# wiring.net
KiCad netlist of a schematic drawn in EAGLE
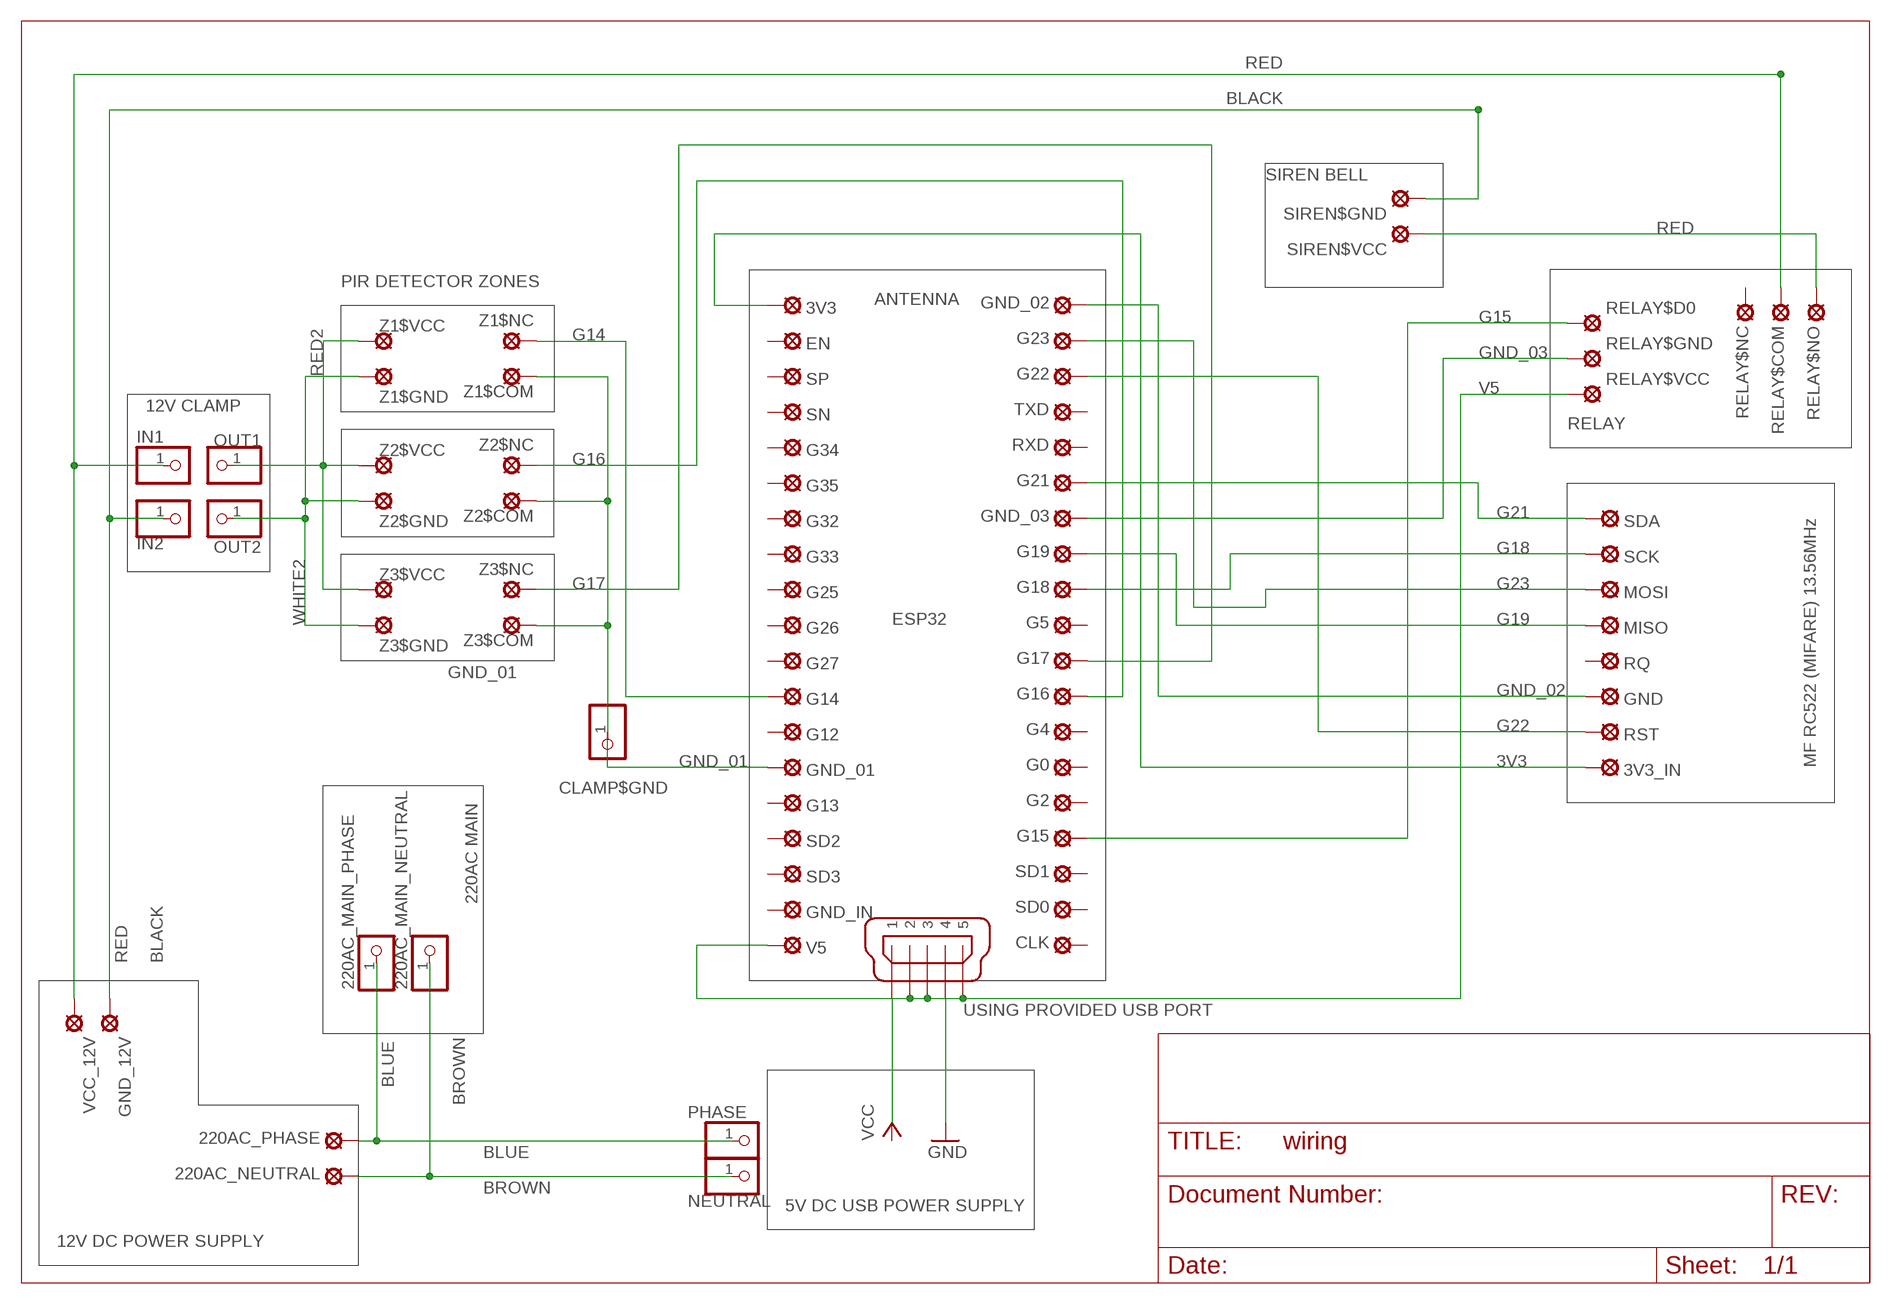
[diagram p0: schematic, sheet 1]

(export (version "E")
  (design (tool "Eeschema 10.0.6"))
  (components
    (comp (ref "3V3")
      (value "MCS08")
      (footprint "eagle-import:MCS08")
      (libsource (lib "eagle-import") (part "MCS08"))
    )
    (comp (ref "3V3_IN")
      (value "MCS08")
      (footprint "eagle-import:MCS08")
      (libsource (lib "eagle-import") (part "MCS08"))
    )
    (comp (ref "220AC_MAIN_NEUTRAL")
      (value "PINHD-1X1")
      (footprint "eagle-import:1X01")
      (libsource (lib "eagle-import") (part "PINHD-1X1"))
    )
    (comp (ref "220AC_MAIN_PHASE")
      (value "PINHD-1X1")
      (footprint "eagle-import:1X01")
      (libsource (lib "eagle-import") (part "PINHD-1X1"))
    )
    (comp (ref "220AC_NEUTRAL")
      (value "MCS08")
      (footprint "eagle-import:MCS08")
      (libsource (lib "eagle-import") (part "MCS08"))
    )
    (comp (ref "220AC_PHASE")
      (value "MCS08")
      (footprint "eagle-import:MCS08")
      (libsource (lib "eagle-import") (part "MCS08"))
    )
    (comp (ref "CLAMP$GND")
      (value "PINHD-1X1")
      (footprint "eagle-import:1X01")
      (libsource (lib "eagle-import") (part "PINHD-1X1"))
    )
    (comp (ref "CLK")
      (value "MCS08")
      (footprint "eagle-import:MCS08")
      (libsource (lib "eagle-import") (part "MCS08"))
    )
    (comp (ref "EN")
      (value "MCS08")
      (footprint "eagle-import:MCS08")
      (libsource (lib "eagle-import") (part "MCS08"))
    )
    (comp (ref "G0")
      (value "MCS08")
      (footprint "eagle-import:MCS08")
      (libsource (lib "eagle-import") (part "MCS08"))
    )
    (comp (ref "G2")
      (value "MCS08")
      (footprint "eagle-import:MCS08")
      (libsource (lib "eagle-import") (part "MCS08"))
    )
    (comp (ref "G4")
      (value "MCS08")
      (footprint "eagle-import:MCS08")
      (libsource (lib "eagle-import") (part "MCS08"))
    )
    (comp (ref "G5")
      (value "MCS08")
      (footprint "eagle-import:MCS08")
      (libsource (lib "eagle-import") (part "MCS08"))
    )
    (comp (ref "G12")
      (value "MCS08")
      (footprint "eagle-import:MCS08")
      (libsource (lib "eagle-import") (part "MCS08"))
    )
    (comp (ref "G13")
      (value "MCS08")
      (footprint "eagle-import:MCS08")
      (libsource (lib "eagle-import") (part "MCS08"))
    )
    (comp (ref "G14")
      (value "MCS08")
      (footprint "eagle-import:MCS08")
      (libsource (lib "eagle-import") (part "MCS08"))
    )
    (comp (ref "G15")
      (value "MCS08")
      (footprint "eagle-import:MCS08")
      (libsource (lib "eagle-import") (part "MCS08"))
    )
    (comp (ref "G16")
      (value "MCS08")
      (footprint "eagle-import:MCS08")
      (libsource (lib "eagle-import") (part "MCS08"))
    )
    (comp (ref "G17")
      (value "MCS08")
      (footprint "eagle-import:MCS08")
      (libsource (lib "eagle-import") (part "MCS08"))
    )
    (comp (ref "G18")
      (value "MCS08")
      (footprint "eagle-import:MCS08")
      (libsource (lib "eagle-import") (part "MCS08"))
    )
    (comp (ref "G19")
      (value "MCS08")
      (footprint "eagle-import:MCS08")
      (libsource (lib "eagle-import") (part "MCS08"))
    )
    (comp (ref "G21")
      (value "MCS08")
      (footprint "eagle-import:MCS08")
      (libsource (lib "eagle-import") (part "MCS08"))
    )
    (comp (ref "G22")
      (value "MCS08")
      (footprint "eagle-import:MCS08")
      (libsource (lib "eagle-import") (part "MCS08"))
    )
    (comp (ref "G23")
      (value "MCS08")
      (footprint "eagle-import:MCS08")
      (libsource (lib "eagle-import") (part "MCS08"))
    )
    (comp (ref "G25")
      (value "MCS08")
      (footprint "eagle-import:MCS08")
      (libsource (lib "eagle-import") (part "MCS08"))
    )
    (comp (ref "G26")
      (value "MCS08")
      (footprint "eagle-import:MCS08")
      (libsource (lib "eagle-import") (part "MCS08"))
    )
    (comp (ref "G27")
      (value "MCS08")
      (footprint "eagle-import:MCS08")
      (libsource (lib "eagle-import") (part "MCS08"))
    )
    (comp (ref "G32")
      (value "MCS08")
      (footprint "eagle-import:MCS08")
      (libsource (lib "eagle-import") (part "MCS08"))
    )
    (comp (ref "G33")
      (value "MCS08")
      (footprint "eagle-import:MCS08")
      (libsource (lib "eagle-import") (part "MCS08"))
    )
    (comp (ref "G34")
      (value "MCS08")
      (footprint "eagle-import:MCS08")
      (libsource (lib "eagle-import") (part "MCS08"))
    )
    (comp (ref "G35")
      (value "MCS08")
      (footprint "eagle-import:MCS08")
      (libsource (lib "eagle-import") (part "MCS08"))
    )
    (comp (ref "GND")
      (value "MCS08")
      (footprint "eagle-import:MCS08")
      (libsource (lib "eagle-import") (part "MCS08"))
    )
    (comp (ref "GND_01")
      (value "MCS08")
      (footprint "eagle-import:MCS08")
      (libsource (lib "eagle-import") (part "MCS08"))
    )
    (comp (ref "GND_02")
      (value "MCS08")
      (footprint "eagle-import:MCS08")
      (libsource (lib "eagle-import") (part "MCS08"))
    )
    (comp (ref "GND_03")
      (value "MCS08")
      (footprint "eagle-import:MCS08")
      (libsource (lib "eagle-import") (part "MCS08"))
    )
    (comp (ref "GND_12V")
      (value "MCS08")
      (footprint "eagle-import:MCS08")
      (libsource (lib "eagle-import") (part "MCS08"))
    )
    (comp (ref "GND_IN")
      (value "MCS08")
      (footprint "eagle-import:MCS08")
      (libsource (lib "eagle-import") (part "MCS08"))
    )
    (comp (ref "IN1")
      (value "PINHD-1X1")
      (footprint "eagle-import:1X01")
      (libsource (lib "eagle-import") (part "PINHD-1X1"))
    )
    (comp (ref "IN2")
      (value "PINHD-1X1")
      (footprint "eagle-import:1X01")
      (libsource (lib "eagle-import") (part "PINHD-1X1"))
    )
    (comp (ref "MISO")
      (value "MCS08")
      (footprint "eagle-import:MCS08")
      (libsource (lib "eagle-import") (part "MCS08"))
    )
    (comp (ref "MOSI")
      (value "MCS08")
      (footprint "eagle-import:MCS08")
      (libsource (lib "eagle-import") (part "MCS08"))
    )
    (comp (ref "NEUTRAL")
      (value "PINHD-1X1")
      (footprint "eagle-import:1X01")
      (libsource (lib "eagle-import") (part "PINHD-1X1"))
    )
    (comp (ref "OUT1")
      (value "PINHD-1X1")
      (footprint "eagle-import:1X01")
      (libsource (lib "eagle-import") (part "PINHD-1X1"))
    )
    (comp (ref "OUT2")
      (value "PINHD-1X1")
      (footprint "eagle-import:1X01")
      (libsource (lib "eagle-import") (part "PINHD-1X1"))
    )
    (comp (ref "PHASE")
      (value "PINHD-1X1")
      (footprint "eagle-import:1X01")
      (libsource (lib "eagle-import") (part "PINHD-1X1"))
    )
    (comp (ref "RELAY$COM")
      (value "MCS08")
      (footprint "eagle-import:MCS08")
      (libsource (lib "eagle-import") (part "MCS08"))
    )
    (comp (ref "RELAY$D0")
      (value "MCS08")
      (footprint "eagle-import:MCS08")
      (libsource (lib "eagle-import") (part "MCS08"))
    )
    (comp (ref "RELAY$GND")
      (value "MCS08")
      (footprint "eagle-import:MCS08")
      (libsource (lib "eagle-import") (part "MCS08"))
    )
    (comp (ref "RELAY$NC")
      (value "MCS08")
      (footprint "eagle-import:MCS08")
      (libsource (lib "eagle-import") (part "MCS08"))
    )
    (comp (ref "RELAY$NO")
      (value "MCS08")
      (footprint "eagle-import:MCS08")
      (libsource (lib "eagle-import") (part "MCS08"))
    )
    (comp (ref "RELAY$VCC")
      (value "MCS08")
      (footprint "eagle-import:MCS08")
      (libsource (lib "eagle-import") (part "MCS08"))
    )
    (comp (ref "RQ")
      (value "MCS08")
      (footprint "eagle-import:MCS08")
      (libsource (lib "eagle-import") (part "MCS08"))
    )
    (comp (ref "RST")
      (value "MCS08")
      (footprint "eagle-import:MCS08")
      (libsource (lib "eagle-import") (part "MCS08"))
    )
    (comp (ref "RXD")
      (value "MCS08")
      (footprint "eagle-import:MCS08")
      (libsource (lib "eagle-import") (part "MCS08"))
    )
    (comp (ref "SCK")
      (value "MCS08")
      (footprint "eagle-import:MCS08")
      (libsource (lib "eagle-import") (part "MCS08"))
    )
    (comp (ref "SD0")
      (value "MCS08")
      (footprint "eagle-import:MCS08")
      (libsource (lib "eagle-import") (part "MCS08"))
    )
    (comp (ref "SD1")
      (value "MCS08")
      (footprint "eagle-import:MCS08")
      (libsource (lib "eagle-import") (part "MCS08"))
    )
    (comp (ref "SD2")
      (value "MCS08")
      (footprint "eagle-import:MCS08")
      (libsource (lib "eagle-import") (part "MCS08"))
    )
    (comp (ref "SD3")
      (value "MCS08")
      (footprint "eagle-import:MCS08")
      (libsource (lib "eagle-import") (part "MCS08"))
    )
    (comp (ref "SDA")
      (value "MCS08")
      (footprint "eagle-import:MCS08")
      (libsource (lib "eagle-import") (part "MCS08"))
    )
    (comp (ref "SIREN$GND")
      (value "MCS08")
      (footprint "eagle-import:MCS08")
      (libsource (lib "eagle-import") (part "MCS08"))
    )
    (comp (ref "SIREN$VCC")
      (value "MCS08")
      (footprint "eagle-import:MCS08")
      (libsource (lib "eagle-import") (part "MCS08"))
    )
    (comp (ref "SN")
      (value "MCS08")
      (footprint "eagle-import:MCS08")
      (libsource (lib "eagle-import") (part "MCS08"))
    )
    (comp (ref "SP")
      (value "MCS08")
      (footprint "eagle-import:MCS08")
      (libsource (lib "eagle-import") (part "MCS08"))
    )
    (comp (ref "TXD")
      (value "MCS08")
      (footprint "eagle-import:MCS08")
      (libsource (lib "eagle-import") (part "MCS08"))
    )
    (comp (ref "V5")
      (value "MCS08")
      (footprint "eagle-import:MCS08")
      (libsource (lib "eagle-import") (part "MCS08"))
    )
    (comp (ref "VCC_12V")
      (value "MCS08")
      (footprint "eagle-import:MCS08")
      (libsource (lib "eagle-import") (part "MCS08"))
    )
    (comp (ref "X1")
      (value "MINI-USB_SHIELD5P2-32005-601")
      (footprint "eagle-import:32005-601")
      (libsource (lib "eagle-import") (part "MINI-USB_SHIELD5P2-32005-601"))
    )
    (comp (ref "Z1$COM")
      (value "MCS08")
      (footprint "eagle-import:MCS08")
      (libsource (lib "eagle-import") (part "MCS08"))
    )
    (comp (ref "Z1$GND")
      (value "MCS08")
      (footprint "eagle-import:MCS08")
      (libsource (lib "eagle-import") (part "MCS08"))
    )
    (comp (ref "Z1$NC")
      (value "MCS08")
      (footprint "eagle-import:MCS08")
      (libsource (lib "eagle-import") (part "MCS08"))
    )
    (comp (ref "Z1$VCC")
      (value "MCS08")
      (footprint "eagle-import:MCS08")
      (libsource (lib "eagle-import") (part "MCS08"))
    )
    (comp (ref "Z2$COM")
      (value "MCS08")
      (footprint "eagle-import:MCS08")
      (libsource (lib "eagle-import") (part "MCS08"))
    )
    (comp (ref "Z2$GND")
      (value "MCS08")
      (footprint "eagle-import:MCS08")
      (libsource (lib "eagle-import") (part "MCS08"))
    )
    (comp (ref "Z2$NC")
      (value "MCS08")
      (footprint "eagle-import:MCS08")
      (libsource (lib "eagle-import") (part "MCS08"))
    )
    (comp (ref "Z2$VCC")
      (value "MCS08")
      (footprint "eagle-import:MCS08")
      (libsource (lib "eagle-import") (part "MCS08"))
    )
    (comp (ref "Z3$COM")
      (value "MCS08")
      (footprint "eagle-import:MCS08")
      (libsource (lib "eagle-import") (part "MCS08"))
    )
    (comp (ref "Z3$GND")
      (value "MCS08")
      (footprint "eagle-import:MCS08")
      (libsource (lib "eagle-import") (part "MCS08"))
    )
    (comp (ref "Z3$NC")
      (value "MCS08")
      (footprint "eagle-import:MCS08")
      (libsource (lib "eagle-import") (part "MCS08"))
    )
    (comp (ref "Z3$VCC")
      (value "MCS08")
      (footprint "eagle-import:MCS08")
      (libsource (lib "eagle-import") (part "MCS08"))
    )
  )
  (nets
    (net (code "1") (name "/3V3") (class "Default")
      (node (ref "3V3") (pin "MP") (pinfunction "MP_MP") (pintype "passive"))
      (node (ref "3V3_IN") (pin "MP") (pinfunction "MP_MP") (pintype "passive"))
    )
    (net (code "2") (name "/BLACK") (class "Default")
      (node (ref "GND_12V") (pin "MP") (pinfunction "MP_MP") (pintype "passive"))
      (node (ref "IN2") (pin "1") (pinfunction "1_1") (pintype "passive"))
      (node (ref "SIREN$GND") (pin "MP") (pinfunction "MP_MP") (pintype "passive"))
    )
    (net (code "3") (name "/BLUE") (class "Default")
      (node (ref "220AC_MAIN_PHASE") (pin "1") (pinfunction "1_1") (pintype "passive"))
      (node (ref "220AC_PHASE") (pin "MP") (pinfunction "MP_MP") (pintype "passive"))
      (node (ref "PHASE") (pin "1") (pinfunction "1_1") (pintype "passive"))
    )
    (net (code "4") (name "/BROWN") (class "Default")
      (node (ref "220AC_MAIN_NEUTRAL") (pin "1") (pinfunction "1_1") (pintype "passive"))
      (node (ref "220AC_NEUTRAL") (pin "MP") (pinfunction "MP_MP") (pintype "passive"))
      (node (ref "NEUTRAL") (pin "1") (pinfunction "1_1") (pintype "passive"))
    )
    (net (code "5") (name "/G14") (class "Default")
      (node (ref "G14") (pin "MP") (pinfunction "MP_MP") (pintype "passive"))
      (node (ref "Z1$NC") (pin "MP") (pinfunction "MP_MP") (pintype "passive"))
    )
    (net (code "6") (name "/G15") (class "Default")
      (node (ref "G15") (pin "MP") (pinfunction "MP_MP") (pintype "passive"))
      (node (ref "RELAY$D0") (pin "MP") (pinfunction "MP_MP") (pintype "passive"))
    )
    (net (code "7") (name "/G16") (class "Default")
      (node (ref "G16") (pin "MP") (pinfunction "MP_MP") (pintype "passive"))
      (node (ref "Z2$NC") (pin "MP") (pinfunction "MP_MP") (pintype "passive"))
    )
    (net (code "8") (name "/G17") (class "Default")
      (node (ref "G17") (pin "MP") (pinfunction "MP_MP") (pintype "passive"))
      (node (ref "Z3$NC") (pin "MP") (pinfunction "MP_MP") (pintype "passive"))
    )
    (net (code "9") (name "/G18") (class "Default")
      (node (ref "G18") (pin "MP") (pinfunction "MP_MP") (pintype "passive"))
      (node (ref "SCK") (pin "MP") (pinfunction "MP_MP") (pintype "passive"))
    )
    (net (code "10") (name "/G19") (class "Default")
      (node (ref "G19") (pin "MP") (pinfunction "MP_MP") (pintype "passive"))
      (node (ref "MISO") (pin "MP") (pinfunction "MP_MP") (pintype "passive"))
    )
    (net (code "11") (name "/G21") (class "Default")
      (node (ref "G21") (pin "MP") (pinfunction "MP_MP") (pintype "passive"))
      (node (ref "SDA") (pin "MP") (pinfunction "MP_MP") (pintype "passive"))
    )
    (net (code "12") (name "/G22") (class "Default")
      (node (ref "G22") (pin "MP") (pinfunction "MP_MP") (pintype "passive"))
      (node (ref "RST") (pin "MP") (pinfunction "MP_MP") (pintype "passive"))
    )
    (net (code "13") (name "/G23") (class "Default")
      (node (ref "G23") (pin "MP") (pinfunction "MP_MP") (pintype "passive"))
      (node (ref "MOSI") (pin "MP") (pinfunction "MP_MP") (pintype "passive"))
    )
    (net (code "14") (name "/GND_01") (class "Default")
      (node (ref "CLAMP$GND") (pin "1") (pinfunction "1_1") (pintype "passive"))
      (node (ref "GND_01") (pin "MP") (pinfunction "MP_MP") (pintype "passive"))
      (node (ref "Z1$COM") (pin "MP") (pinfunction "MP_MP") (pintype "passive"))
      (node (ref "Z2$COM") (pin "MP") (pinfunction "MP_MP") (pintype "passive"))
      (node (ref "Z3$COM") (pin "MP") (pinfunction "MP_MP") (pintype "passive"))
    )
    (net (code "15") (name "/GND_02") (class "Default")
      (node (ref "GND") (pin "MP") (pinfunction "MP_MP") (pintype "passive"))
      (node (ref "GND_02") (pin "MP") (pinfunction "MP_MP") (pintype "passive"))
    )
    (net (code "16") (name "/GND_03") (class "Default")
      (node (ref "GND_03") (pin "MP") (pinfunction "MP_MP") (pintype "passive"))
      (node (ref "RELAY$GND") (pin "MP") (pinfunction "MP_MP") (pintype "passive"))
    )
    (net (code "17") (name "/RED") (class "Default")
      (node (ref "IN1") (pin "1") (pinfunction "1_1") (pintype "passive"))
      (node (ref "RELAY$COM") (pin "MP") (pinfunction "MP_MP") (pintype "passive"))
      (node (ref "RELAY$NO") (pin "MP") (pinfunction "MP_MP") (pintype "passive"))
      (node (ref "SIREN$VCC") (pin "MP") (pinfunction "MP_MP") (pintype "passive"))
      (node (ref "VCC_12V") (pin "MP") (pinfunction "MP_MP") (pintype "passive"))
    )
    (net (code "18") (name "/RED2") (class "Default")
      (node (ref "OUT1") (pin "1") (pinfunction "1_1") (pintype "passive"))
      (node (ref "Z1$VCC") (pin "MP") (pinfunction "MP_MP") (pintype "passive"))
      (node (ref "Z2$VCC") (pin "MP") (pinfunction "MP_MP") (pintype "passive"))
      (node (ref "Z3$VCC") (pin "MP") (pinfunction "MP_MP") (pintype "passive"))
    )
    (net (code "19") (name "/V5") (class "Default")
      (node (ref "RELAY$VCC") (pin "MP") (pinfunction "MP_MP") (pintype "passive"))
      (node (ref "V5") (pin "MP") (pinfunction "MP_MP") (pintype "passive"))
      (node (ref "X1") (pin "2") (pinfunction "2_2") (pintype "passive"))
      (node (ref "X1") (pin "3") (pinfunction "3_3") (pintype "passive"))
      (node (ref "X1") (pin "5") (pinfunction "5_5") (pintype "passive"))
    )
    (net (code "20") (name "/WHITE2") (class "Default")
      (node (ref "OUT2") (pin "1") (pinfunction "1_1") (pintype "passive"))
      (node (ref "Z1$GND") (pin "MP") (pinfunction "MP_MP") (pintype "passive"))
      (node (ref "Z2$GND") (pin "MP") (pinfunction "MP_MP") (pintype "passive"))
      (node (ref "Z3$GND") (pin "MP") (pinfunction "MP_MP") (pintype "passive"))
    )
    (net (code "21") (name "GND") (class "Default")
      (node (ref "X1") (pin "4") (pinfunction "4_4") (pintype "passive"))
    )
    (net (code "23") (name "unconnected-(CLK-PadMP)") (class "Default")
      (node (ref "CLK") (pin "MP") (pinfunction "MP_MP") (pintype "passive"))
    )
    (net (code "24") (name "unconnected-(EN-PadMP)") (class "Default")
      (node (ref "EN") (pin "MP") (pinfunction "MP_MP") (pintype "passive"))
    )
    (net (code "25") (name "unconnected-(G0-PadMP)") (class "Default")
      (node (ref "G0") (pin "MP") (pinfunction "MP_MP") (pintype "passive"))
    )
    (net (code "26") (name "unconnected-(G2-PadMP)") (class "Default")
      (node (ref "G2") (pin "MP") (pinfunction "MP_MP") (pintype "passive"))
    )
    (net (code "27") (name "unconnected-(G4-PadMP)") (class "Default")
      (node (ref "G4") (pin "MP") (pinfunction "MP_MP") (pintype "passive"))
    )
    (net (code "28") (name "unconnected-(G5-PadMP)") (class "Default")
      (node (ref "G5") (pin "MP") (pinfunction "MP_MP") (pintype "passive"))
    )
    (net (code "29") (name "unconnected-(G12-PadMP)") (class "Default")
      (node (ref "G12") (pin "MP") (pinfunction "MP_MP") (pintype "passive"))
    )
    (net (code "30") (name "unconnected-(G13-PadMP)") (class "Default")
      (node (ref "G13") (pin "MP") (pinfunction "MP_MP") (pintype "passive"))
    )
    (net (code "31") (name "unconnected-(G25-PadMP)") (class "Default")
      (node (ref "G25") (pin "MP") (pinfunction "MP_MP") (pintype "passive"))
    )
    (net (code "32") (name "unconnected-(G26-PadMP)") (class "Default")
      (node (ref "G26") (pin "MP") (pinfunction "MP_MP") (pintype "passive"))
    )
    (net (code "33") (name "unconnected-(G27-PadMP)") (class "Default")
      (node (ref "G27") (pin "MP") (pinfunction "MP_MP") (pintype "passive"))
    )
    (net (code "34") (name "unconnected-(G32-PadMP)") (class "Default")
      (node (ref "G32") (pin "MP") (pinfunction "MP_MP") (pintype "passive"))
    )
    (net (code "35") (name "unconnected-(G33-PadMP)") (class "Default")
      (node (ref "G33") (pin "MP") (pinfunction "MP_MP") (pintype "passive"))
    )
    (net (code "36") (name "unconnected-(G34-PadMP)") (class "Default")
      (node (ref "G34") (pin "MP") (pinfunction "MP_MP") (pintype "passive"))
    )
    (net (code "37") (name "unconnected-(G35-PadMP)") (class "Default")
      (node (ref "G35") (pin "MP") (pinfunction "MP_MP") (pintype "passive"))
    )
    (net (code "38") (name "unconnected-(GND_IN-PadMP)") (class "Default")
      (node (ref "GND_IN") (pin "MP") (pinfunction "MP_MP") (pintype "passive"))
    )
    (net (code "39") (name "unconnected-(RELAY$NC-PadMP)") (class "Default")
      (node (ref "RELAY$NC") (pin "MP") (pinfunction "MP_MP") (pintype "passive"))
    )
    (net (code "40") (name "unconnected-(RQ-PadMP)") (class "Default")
      (node (ref "RQ") (pin "MP") (pinfunction "MP_MP") (pintype "passive"))
    )
    (net (code "41") (name "unconnected-(RXD-PadMP)") (class "Default")
      (node (ref "RXD") (pin "MP") (pinfunction "MP_MP") (pintype "passive"))
    )
    (net (code "42") (name "unconnected-(SD0-PadMP)") (class "Default")
      (node (ref "SD0") (pin "MP") (pinfunction "MP_MP") (pintype "passive"))
    )
    (net (code "43") (name "unconnected-(SD1-PadMP)") (class "Default")
      (node (ref "SD1") (pin "MP") (pinfunction "MP_MP") (pintype "passive"))
    )
    (net (code "44") (name "unconnected-(SD2-PadMP)") (class "Default")
      (node (ref "SD2") (pin "MP") (pinfunction "MP_MP") (pintype "passive"))
    )
    (net (code "45") (name "unconnected-(SD3-PadMP)") (class "Default")
      (node (ref "SD3") (pin "MP") (pinfunction "MP_MP") (pintype "passive"))
    )
    (net (code "46") (name "unconnected-(SN-PadMP)") (class "Default")
      (node (ref "SN") (pin "MP") (pinfunction "MP_MP") (pintype "passive"))
    )
    (net (code "47") (name "unconnected-(SP-PadMP)") (class "Default")
      (node (ref "SP") (pin "MP") (pinfunction "MP_MP") (pintype "passive"))
    )
    (net (code "48") (name "unconnected-(TXD-PadMP)") (class "Default")
      (node (ref "TXD") (pin "MP") (pinfunction "MP_MP") (pintype "passive"))
    )
    (net (code "49") (name "unconnected-(X1-Pad1)") (class "Default")
      (node (ref "X1") (pin "1") (pinfunction "1_1") (pintype "passive"))
    )
  )
)
